# modem.net
KiCad netlist of a schematic drawn in EAGLE
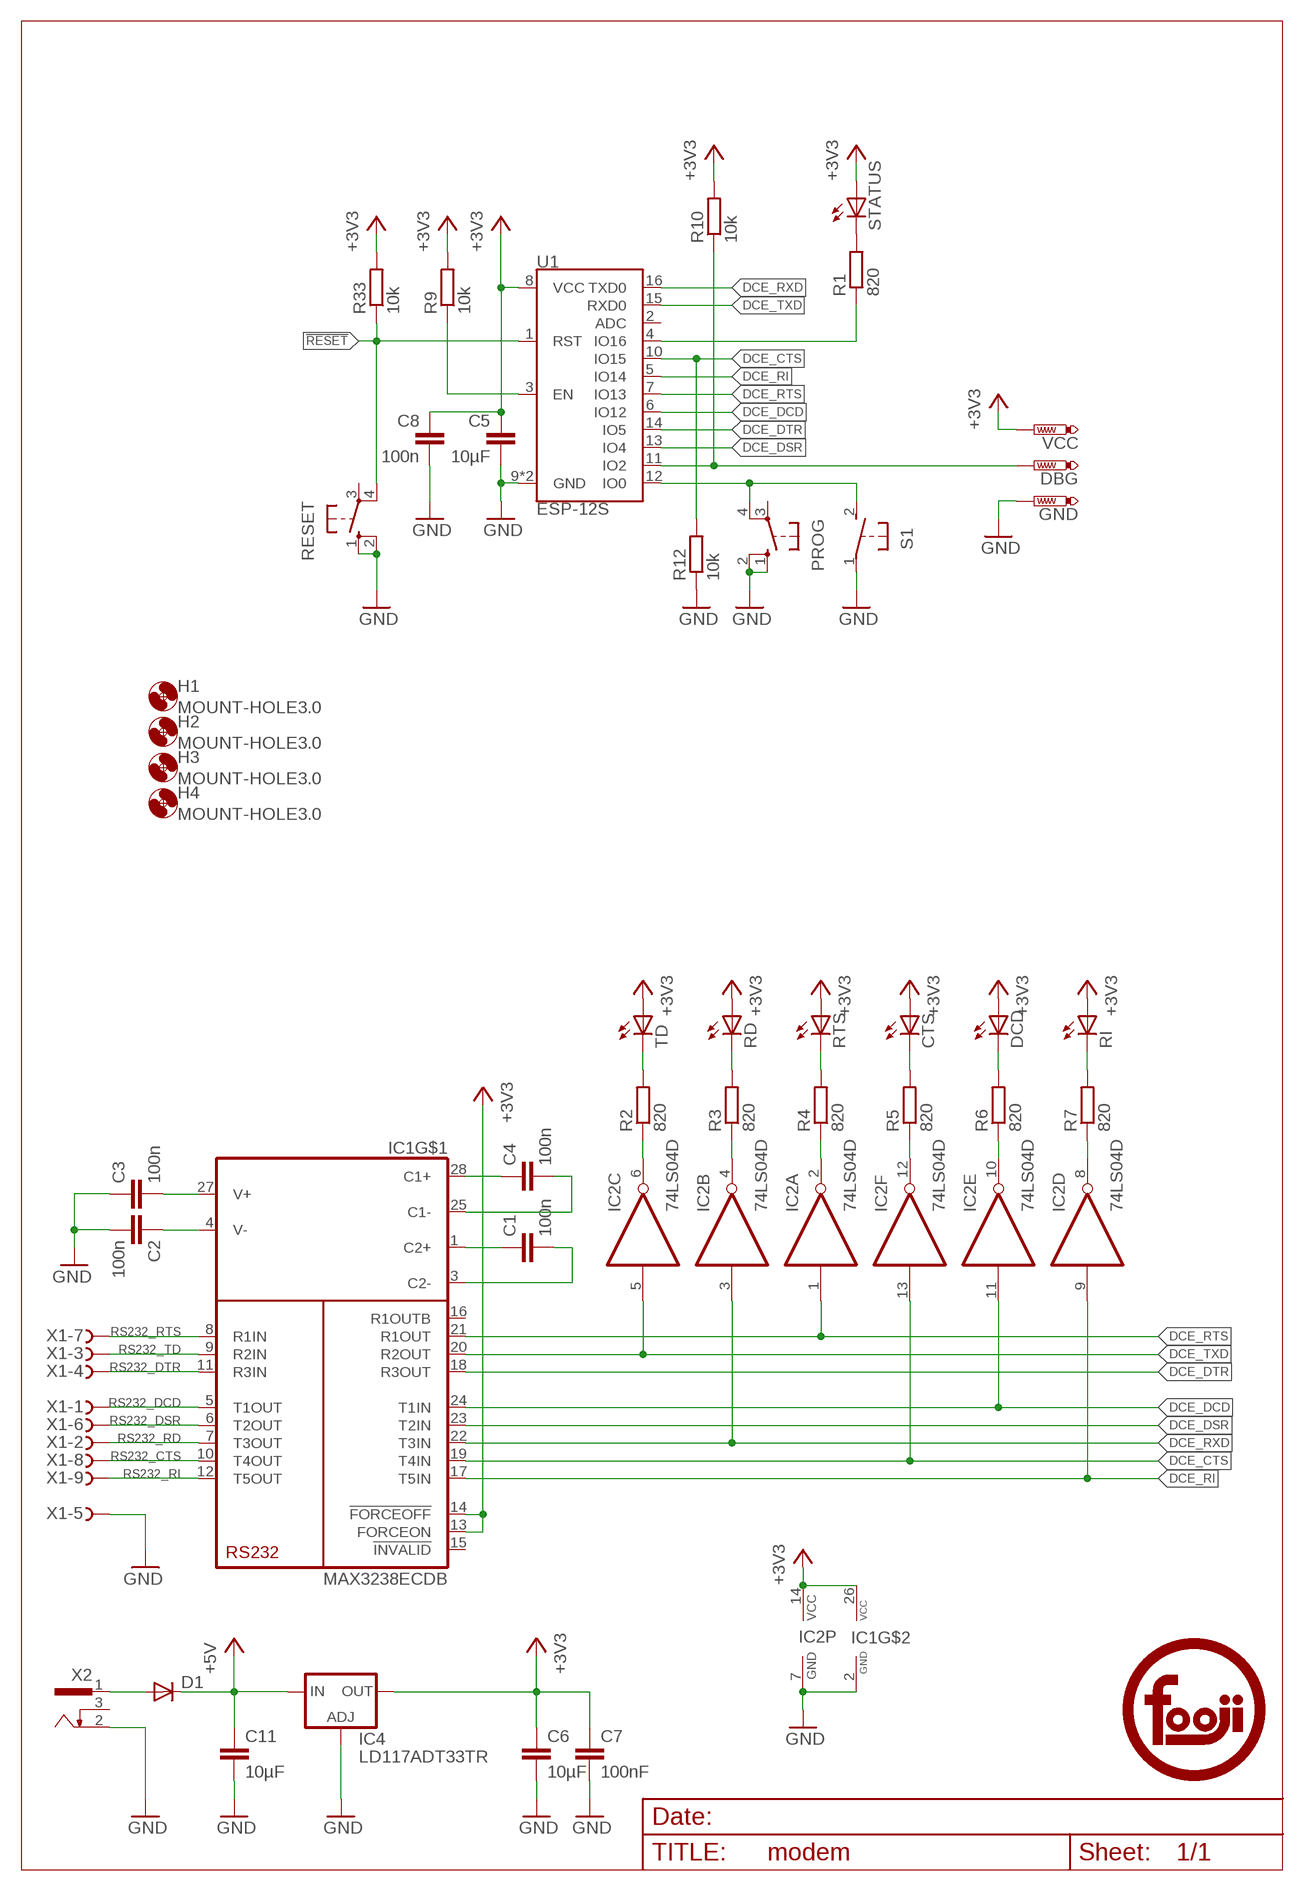
[diagram p0: schematic, sheet 1]

(export (version "E")
  (design (tool "Eeschema 10.0.6"))
  (components
    (comp (ref "C1")
      (value "100n")
      (footprint "eagle-import:C0805")
      (libsource (lib "eagle-import") (part "C-EUC0805"))
    )
    (comp (ref "C2")
      (value "100n")
      (footprint "eagle-import:C0805")
      (libsource (lib "eagle-import") (part "C-EUC0805"))
    )
    (comp (ref "C3")
      (value "100n")
      (footprint "eagle-import:C0805")
      (libsource (lib "eagle-import") (part "C-EUC0805"))
    )
    (comp (ref "C4")
      (value "100n")
      (footprint "eagle-import:C0805")
      (libsource (lib "eagle-import") (part "C-EUC0805"))
    )
    (comp (ref "C5")
      (value "10µF")
      (footprint "eagle-import:C0805")
      (libsource (lib "eagle-import") (part "C-EUC0805"))
    )
    (comp (ref "C6")
      (value "10µF")
      (footprint "eagle-import:C0805")
      (libsource (lib "eagle-import") (part "C-EUC0805"))
    )
    (comp (ref "C7")
      (value "100nF")
      (footprint "eagle-import:C0805")
      (libsource (lib "eagle-import") (part "C-EUC0805"))
    )
    (comp (ref "C8")
      (value "100n")
      (footprint "eagle-import:C0805")
      (libsource (lib "eagle-import") (part "C-EUC0805"))
    )
    (comp (ref "C11")
      (value "10µF")
      (footprint "eagle-import:C0805")
      (libsource (lib "eagle-import") (part "C-EUC0805"))
    )
    (comp (ref "CTS")
      (value "LED5MM")
      (footprint "eagle-import:LED5MM")
      (libsource (lib "eagle-import") (part "LED5MM"))
    )
    (comp (ref "D1")
      (value "DIODE-SMB")
      (footprint "eagle-import:SMB")
      (libsource (lib "eagle-import") (part "DIODE-SMB"))
    )
    (comp (ref "DBG")
      (value "PTR1PAD1-13")
      (footprint "eagle-import:P1-13")
      (libsource (lib "eagle-import") (part "PTR1PAD1-13"))
    )
    (comp (ref "DCD")
      (value "LED5MM")
      (footprint "eagle-import:LED5MM")
      (libsource (lib "eagle-import") (part "LED5MM"))
    )
    (comp (ref "GND")
      (value "PTR1PAD1-13")
      (footprint "eagle-import:P1-13")
      (libsource (lib "eagle-import") (part "PTR1PAD1-13"))
    )
    (comp (ref "H1")
      (value "MOUNT-HOLE3.0")
      (footprint "eagle-import:3,0")
      (libsource (lib "eagle-import") (part "MOUNT-HOLE3.0"))
    )
    (comp (ref "H2")
      (value "MOUNT-HOLE3.0")
      (footprint "eagle-import:3,0")
      (libsource (lib "eagle-import") (part "MOUNT-HOLE3.0"))
    )
    (comp (ref "H3")
      (value "MOUNT-HOLE3.0")
      (footprint "eagle-import:3,0")
      (libsource (lib "eagle-import") (part "MOUNT-HOLE3.0"))
    )
    (comp (ref "H4")
      (value "MOUNT-HOLE3.0")
      (footprint "eagle-import:3,0")
      (libsource (lib "eagle-import") (part "MOUNT-HOLE3.0"))
    )
    (comp (ref "IC1")
      (value "MAX3238ECDB")
      (footprint "eagle-import:SSOP28")
      (libsource (lib "eagle-import") (part "MAX3238ECDB"))
    )
    (comp (ref "IC2")
      (value "74LS04D")
      (footprint "eagle-import:SO14")
      (libsource (lib "eagle-import") (part "7404DLS"))
    )
    (comp (ref "IC4")
      (value "LD117ADT33TR")
      (footprint "eagle-import:DPACK")
      (libsource (lib "eagle-import") (part "LD117A?DT33TR"))
    )
    (comp (ref "PROG")
      (value "10-XX")
      (footprint "eagle-import:B3F-10XX")
      (fields (field (name "MPN") "B3F-1000"))
      (libsource (lib "eagle-import") (part "10-XX"))
    )
    (comp (ref "R1")
      (value "820")
      (footprint "eagle-import:R0805")
      (libsource (lib "eagle-import") (part "R-EU_R0805"))
    )
    (comp (ref "R2")
      (value "820")
      (footprint "eagle-import:R0805")
      (libsource (lib "eagle-import") (part "R-EU_R0805"))
    )
    (comp (ref "R3")
      (value "820")
      (footprint "eagle-import:R0805")
      (libsource (lib "eagle-import") (part "R-EU_R0805"))
    )
    (comp (ref "R4")
      (value "820")
      (footprint "eagle-import:R0805")
      (libsource (lib "eagle-import") (part "R-EU_R0805"))
    )
    (comp (ref "R5")
      (value "820")
      (footprint "eagle-import:R0805")
      (libsource (lib "eagle-import") (part "R-EU_R0805"))
    )
    (comp (ref "R6")
      (value "820")
      (footprint "eagle-import:R0805")
      (libsource (lib "eagle-import") (part "R-EU_R0805"))
    )
    (comp (ref "R7")
      (value "820")
      (footprint "eagle-import:R0805")
      (libsource (lib "eagle-import") (part "R-EU_R0805"))
    )
    (comp (ref "R9")
      (value "10k")
      (footprint "eagle-import:R0805")
      (libsource (lib "eagle-import") (part "R-EU_R0805"))
    )
    (comp (ref "R10")
      (value "10k")
      (footprint "eagle-import:R0805")
      (libsource (lib "eagle-import") (part "R-EU_R0805"))
    )
    (comp (ref "R12")
      (value "10k")
      (footprint "eagle-import:R0805")
      (libsource (lib "eagle-import") (part "R-EU_R0805"))
    )
    (comp (ref "R33")
      (value "10k")
      (footprint "eagle-import:R0805")
      (libsource (lib "eagle-import") (part "R-EU_R0805"))
    )
    (comp (ref "RD")
      (value "LED5MM")
      (footprint "eagle-import:LED5MM")
      (libsource (lib "eagle-import") (part "LED5MM"))
    )
    (comp (ref "RESET")
      (value "10-XX")
      (footprint "eagle-import:B3F-10XX")
      (fields (field (name "MPN") "B3F-1000"))
      (libsource (lib "eagle-import") (part "10-XX"))
    )
    (comp (ref "RI")
      (value "LED5MM")
      (footprint "eagle-import:LED5MM")
      (libsource (lib "eagle-import") (part "LED5MM"))
    )
    (comp (ref "RTS")
      (value "LED5MM")
      (footprint "eagle-import:LED5MM")
      (libsource (lib "eagle-import") (part "LED5MM"))
    )
    (comp (ref "S1")
      (value "31-XX")
      (footprint "eagle-import:B3F-31XX")
      (fields (field (name "MPN") "B3F-3100"))
      (libsource (lib "eagle-import") (part "31-XX"))
    )
    (comp (ref "STATUS")
      (value "LED5MM")
      (footprint "eagle-import:LED5MM")
      (libsource (lib "eagle-import") (part "LED5MM"))
    )
    (comp (ref "TD")
      (value "LED5MM")
      (footprint "eagle-import:LED5MM")
      (libsource (lib "eagle-import") (part "LED5MM"))
    )
    (comp (ref "U$3")
      (value "LOGOTOP_NOCIRCLE_TSTOP")
      (footprint "eagle-import:LOGO_TOP_NOCIRCLE_TSTOP")
      (libsource (lib "eagle-import") (part "LOGOTOP_NOCIRCLE_TSTOP"))
    )
    (comp (ref "U1")
      (value "ESP-12S")
      (footprint "eagle-import:ESP-12S")
      (libsource (lib "eagle-import") (part "ESP-12S"))
    )
    (comp (ref "VCC")
      (value "PTR1PAD1-13")
      (footprint "eagle-import:P1-13")
      (libsource (lib "eagle-import") (part "PTR1PAD1-13"))
    )
    (comp (ref "X1")
      (value "F09HPS")
      (footprint "eagle-import:F09HP")
      (libsource (lib "eagle-import") (part "F09HPS"))
    )
    (comp (ref "X2")
      (value "733980-62")
      (footprint "eagle-import:733980-62")
      (libsource (lib "eagle-import") (part "73398?0-62"))
    )
  )
  (nets
    (net (code "1") (name "+3V3") (class "Default")
      (node (ref "C5") (pin "1") (pinfunction "1_1") (pintype "passive"))
      (node (ref "C6") (pin "1") (pinfunction "1_1") (pintype "passive"))
      (node (ref "C7") (pin "1") (pinfunction "1_1") (pintype "passive"))
      (node (ref "C8") (pin "1") (pinfunction "1_1") (pintype "passive"))
      (node (ref "CTS") (pin "A") (pinfunction "A_A") (pintype "passive"))
      (node (ref "DCD") (pin "A") (pinfunction "A_A") (pintype "passive"))
      (node (ref "IC1") (pin "13") (pinfunction "FORCEON_13") (pintype "input"))
      (node (ref "IC1") (pin "14") (pinfunction "~{FORCEOFF}_14") (pintype "input"))
      (node (ref "IC1") (pin "26") (pinfunction "VCC_26") (pintype "power_in"))
      (node (ref "IC2") (pin "14") (pinfunction "VCC_14") (pintype "power_in"))
      (node (ref "IC4") (pin "4") (pinfunction "OUT_4") (pintype "passive"))
      (node (ref "R10") (pin "2") (pinfunction "2_2") (pintype "passive"))
      (node (ref "R33") (pin "2") (pinfunction "2_2") (pintype "passive"))
      (node (ref "R9") (pin "2") (pinfunction "2_2") (pintype "passive"))
      (node (ref "RD") (pin "A") (pinfunction "A_A") (pintype "passive"))
      (node (ref "RI") (pin "A") (pinfunction "A_A") (pintype "passive"))
      (node (ref "RTS") (pin "A") (pinfunction "A_A") (pintype "passive"))
      (node (ref "STATUS") (pin "A") (pinfunction "A_A") (pintype "passive"))
      (node (ref "TD") (pin "A") (pinfunction "A_A") (pintype "passive"))
      (node (ref "U1") (pin "8") (pinfunction "VCC_8") (pintype "bidirectional"))
      (node (ref "VCC") (pin "TP") (pinfunction "TP_TP") (pintype "input"))
    )
    (net (code "2") (name "+5V") (class "Default")
      (node (ref "C11") (pin "1") (pinfunction "1_1") (pintype "passive"))
      (node (ref "D1") (pin "C") (pinfunction "C_C") (pintype "passive"))
      (node (ref "IC4") (pin "3") (pinfunction "IN_3") (pintype "input"))
    )
    (net (code "3") (name "/RS232_CTS") (class "Default")
      (node (ref "IC1") (pin "10") (pinfunction "T4OUT_10") (pintype "input"))
      (node (ref "X1") (pin "8") (pinfunction "F_8") (pintype "passive"))
    )
    (net (code "4") (name "/RS232_DCD") (class "Default")
      (node (ref "IC1") (pin "5") (pinfunction "T1OUT_5") (pintype "output"))
      (node (ref "X1") (pin "1") (pinfunction "F_1") (pintype "passive"))
    )
    (net (code "5") (name "/RS232_DSR") (class "Default")
      (node (ref "IC1") (pin "6") (pinfunction "T2OUT_6") (pintype "output"))
      (node (ref "X1") (pin "6") (pinfunction "F_6") (pintype "passive"))
    )
    (net (code "6") (name "/RS232_DTR") (class "Default")
      (node (ref "IC1") (pin "11") (pinfunction "R3IN_11") (pintype "input"))
      (node (ref "X1") (pin "4") (pinfunction "F_4") (pintype "passive"))
    )
    (net (code "7") (name "/RS232_RD") (class "Default")
      (node (ref "IC1") (pin "7") (pinfunction "T3OUT_7") (pintype "output"))
      (node (ref "X1") (pin "2") (pinfunction "F_2") (pintype "passive"))
    )
    (net (code "8") (name "/RS232_RI") (class "Default")
      (node (ref "IC1") (pin "12") (pinfunction "T5OUT_12") (pintype "input"))
      (node (ref "X1") (pin "9") (pinfunction "F_9") (pintype "passive"))
    )
    (net (code "9") (name "/RS232_RTS") (class "Default")
      (node (ref "IC1") (pin "8") (pinfunction "R1IN_8") (pintype "input"))
      (node (ref "X1") (pin "7") (pinfunction "F_7") (pintype "passive"))
    )
    (net (code "10") (name "/RS232_TD") (class "Default")
      (node (ref "IC1") (pin "9") (pinfunction "R2IN_9") (pintype "input"))
      (node (ref "X1") (pin "3") (pinfunction "F_3") (pintype "passive"))
    )
    (net (code "11") (name "/~{RESET}") (class "Default")
      (node (ref "R33") (pin "1") (pinfunction "1_1") (pintype "passive"))
      (node (ref "RESET") (pin "4") (pinfunction "P1_4") (pintype "passive"))
      (node (ref "U1") (pin "1") (pinfunction "RST_1") (pintype "bidirectional"))
    )
    (net (code "12") (name "DCE_CTS") (class "Default")
      (node (ref "IC1") (pin "19") (pinfunction "T4IN_19") (pintype "output"))
      (node (ref "IC2") (pin "13") (pinfunction "I_13") (pintype "input"))
      (node (ref "R12") (pin "2") (pinfunction "2_2") (pintype "passive"))
      (node (ref "U1") (pin "10") (pinfunction "IO15_10") (pintype "bidirectional"))
    )
    (net (code "13") (name "DCE_DCD") (class "Default")
      (node (ref "IC1") (pin "24") (pinfunction "T1IN_24") (pintype "input"))
      (node (ref "IC2") (pin "11") (pinfunction "I_11") (pintype "input"))
      (node (ref "U1") (pin "6") (pinfunction "IO12_6") (pintype "bidirectional"))
    )
    (net (code "14") (name "DCE_DSR") (class "Default")
      (node (ref "IC1") (pin "23") (pinfunction "T2IN_23") (pintype "input"))
      (node (ref "U1") (pin "13") (pinfunction "IO4_13") (pintype "bidirectional"))
    )
    (net (code "15") (name "DCE_DTR") (class "Default")
      (node (ref "IC1") (pin "18") (pinfunction "R3OUT_18") (pintype "output"))
      (node (ref "U1") (pin "14") (pinfunction "IO5_14") (pintype "bidirectional"))
    )
    (net (code "16") (name "DCE_RI") (class "Default")
      (node (ref "IC1") (pin "17") (pinfunction "T5IN_17") (pintype "output"))
      (node (ref "IC2") (pin "9") (pinfunction "I_9") (pintype "input"))
      (node (ref "U1") (pin "5") (pinfunction "IO14_5") (pintype "bidirectional"))
    )
    (net (code "17") (name "DCE_RTS") (class "Default")
      (node (ref "IC1") (pin "21") (pinfunction "R1OUT_21") (pintype "output"))
      (node (ref "IC2") (pin "1") (pinfunction "I_1") (pintype "input"))
      (node (ref "U1") (pin "7") (pinfunction "IO13_7") (pintype "bidirectional"))
    )
    (net (code "18") (name "DCE_RXD") (class "Default")
      (node (ref "IC1") (pin "22") (pinfunction "T3IN_22") (pintype "input"))
      (node (ref "IC2") (pin "3") (pinfunction "I_3") (pintype "input"))
      (node (ref "U1") (pin "16") (pinfunction "TXD0_16") (pintype "bidirectional"))
    )
    (net (code "19") (name "DCE_TXD") (class "Default")
      (node (ref "IC1") (pin "20") (pinfunction "R2OUT_20") (pintype "output"))
      (node (ref "IC2") (pin "5") (pinfunction "I_5") (pintype "input"))
      (node (ref "U1") (pin "15") (pinfunction "RXD0_15") (pintype "bidirectional"))
    )
    (net (code "20") (name "GND") (class "Default")
      (node (ref "C11") (pin "2") (pinfunction "2_2") (pintype "passive"))
      (node (ref "C2") (pin "2") (pinfunction "2_2") (pintype "passive"))
      (node (ref "C3") (pin "1") (pinfunction "1_1") (pintype "passive"))
      (node (ref "C5") (pin "2") (pinfunction "2_2") (pintype "passive"))
      (node (ref "C6") (pin "2") (pinfunction "2_2") (pintype "passive"))
      (node (ref "C7") (pin "2") (pinfunction "2_2") (pintype "passive"))
      (node (ref "C8") (pin "2") (pinfunction "2_2") (pintype "passive"))
      (node (ref "GND") (pin "TP") (pinfunction "TP_TP") (pintype "input"))
      (node (ref "IC1") (pin "2") (pinfunction "GND_2") (pintype "power_in"))
      (node (ref "IC2") (pin "7") (pinfunction "GND_7") (pintype "power_in"))
      (node (ref "IC4") (pin "1") (pinfunction "ADJ_1") (pintype "input"))
      (node (ref "PROG") (pin "1") (pinfunction "S_1") (pintype "passive"))
      (node (ref "PROG") (pin "2") (pinfunction "S1_2") (pintype "passive"))
      (node (ref "R12") (pin "1") (pinfunction "1_1") (pintype "passive"))
      (node (ref "RESET") (pin "1") (pinfunction "S_1") (pintype "passive"))
      (node (ref "RESET") (pin "2") (pinfunction "S1_2") (pintype "passive"))
      (node (ref "S1") (pin "1") (pinfunction "P_1") (pintype "passive"))
      (node (ref "U1") (pin "9") (pinfunction "GND_9") (pintype "bidirectional"))
      (node (ref "U1") (pin "P$1") (pinfunction "GND_P$1") (pintype "bidirectional"))
      (node (ref "X1") (pin "5") (pinfunction "F_5") (pintype "passive"))
      (node (ref "X2") (pin "2") (pinfunction "2_2") (pintype "passive"))
    )
    (net (code "21") (name "Net-(CTS-C)") (class "Default")
      (node (ref "CTS") (pin "K") (pinfunction "C_K") (pintype "passive"))
      (node (ref "R5") (pin "2") (pinfunction "2_2") (pintype "passive"))
    )
    (net (code "22") (name "Net-(D1-PadA)") (class "Default")
      (node (ref "D1") (pin "A") (pinfunction "A_A") (pintype "passive"))
      (node (ref "X2") (pin "1") (pinfunction "1_1") (pintype "passive"))
    )
    (net (code "23") (name "Net-(DCD-C)") (class "Default")
      (node (ref "DCD") (pin "K") (pinfunction "C_K") (pintype "passive"))
      (node (ref "R6") (pin "2") (pinfunction "2_2") (pintype "passive"))
    )
    (net (code "24") (name "Net-(IC1A-C1+)") (class "Default")
      (node (ref "C4") (pin "1") (pinfunction "1_1") (pintype "passive"))
      (node (ref "IC1") (pin "28") (pinfunction "C1+_28") (pintype "passive"))
    )
    (net (code "25") (name "Net-(IC1A-C1-)") (class "Default")
      (node (ref "C4") (pin "2") (pinfunction "2_2") (pintype "passive"))
      (node (ref "IC1") (pin "25") (pinfunction "C1-_25") (pintype "passive"))
    )
    (net (code "26") (name "Net-(IC1A-C2+)") (class "Default")
      (node (ref "C1") (pin "1") (pinfunction "1_1") (pintype "passive"))
      (node (ref "IC1") (pin "1") (pinfunction "C2+_1") (pintype "passive"))
    )
    (net (code "27") (name "Net-(IC1A-C2-)") (class "Default")
      (node (ref "C1") (pin "2") (pinfunction "2_2") (pintype "passive"))
      (node (ref "IC1") (pin "3") (pinfunction "C2-_3") (pintype "passive"))
    )
    (net (code "28") (name "Net-(IC1A-V+)") (class "Default")
      (node (ref "C3") (pin "2") (pinfunction "2_2") (pintype "passive"))
      (node (ref "IC1") (pin "27") (pinfunction "V+_27") (pintype "passive"))
    )
    (net (code "29") (name "Net-(IC1A-V-)") (class "Default")
      (node (ref "C2") (pin "1") (pinfunction "1_1") (pintype "passive"))
      (node (ref "IC1") (pin "4") (pinfunction "V-_4") (pintype "passive"))
    )
    (net (code "30") (name "Net-(IC2A-O)") (class "Default")
      (node (ref "IC2") (pin "2") (pinfunction "O_2") (pintype "output"))
      (node (ref "R4") (pin "1") (pinfunction "1_1") (pintype "passive"))
    )
    (net (code "31") (name "Net-(IC2B-O)") (class "Default")
      (node (ref "IC2") (pin "4") (pinfunction "O_4") (pintype "output"))
      (node (ref "R3") (pin "1") (pinfunction "1_1") (pintype "passive"))
    )
    (net (code "32") (name "Net-(IC2C-O)") (class "Default")
      (node (ref "IC2") (pin "6") (pinfunction "O_6") (pintype "output"))
      (node (ref "R2") (pin "1") (pinfunction "1_1") (pintype "passive"))
    )
    (net (code "33") (name "Net-(IC2D-O)") (class "Default")
      (node (ref "IC2") (pin "8") (pinfunction "O_8") (pintype "output"))
      (node (ref "R7") (pin "1") (pinfunction "1_1") (pintype "passive"))
    )
    (net (code "34") (name "Net-(IC2E-O)") (class "Default")
      (node (ref "IC2") (pin "10") (pinfunction "O_10") (pintype "output"))
      (node (ref "R6") (pin "1") (pinfunction "1_1") (pintype "passive"))
    )
    (net (code "35") (name "Net-(IC2F-O)") (class "Default")
      (node (ref "IC2") (pin "12") (pinfunction "O_12") (pintype "output"))
      (node (ref "R5") (pin "1") (pinfunction "1_1") (pintype "passive"))
    )
    (net (code "36") (name "Net-(PROG-P1)") (class "Default")
      (node (ref "PROG") (pin "4") (pinfunction "P1_4") (pintype "passive"))
      (node (ref "S1") (pin "2") (pinfunction "S_2") (pintype "passive"))
      (node (ref "U1") (pin "12") (pinfunction "IO0_12") (pintype "bidirectional"))
    )
    (net (code "37") (name "Net-(RD-C)") (class "Default")
      (node (ref "R3") (pin "2") (pinfunction "2_2") (pintype "passive"))
      (node (ref "RD") (pin "K") (pinfunction "C_K") (pintype "passive"))
    )
    (net (code "38") (name "Net-(RI-C)") (class "Default")
      (node (ref "R7") (pin "2") (pinfunction "2_2") (pintype "passive"))
      (node (ref "RI") (pin "K") (pinfunction "C_K") (pintype "passive"))
    )
    (net (code "39") (name "Net-(RTS-C)") (class "Default")
      (node (ref "R4") (pin "2") (pinfunction "2_2") (pintype "passive"))
      (node (ref "RTS") (pin "K") (pinfunction "C_K") (pintype "passive"))
    )
    (net (code "40") (name "Net-(STATUS-C)") (class "Default")
      (node (ref "R1") (pin "2") (pinfunction "2_2") (pintype "passive"))
      (node (ref "STATUS") (pin "K") (pinfunction "C_K") (pintype "passive"))
    )
    (net (code "41") (name "Net-(TD-C)") (class "Default")
      (node (ref "R2") (pin "2") (pinfunction "2_2") (pintype "passive"))
      (node (ref "TD") (pin "K") (pinfunction "C_K") (pintype "passive"))
    )
    (net (code "42") (name "Net-(U1-EN)") (class "Default")
      (node (ref "R9") (pin "1") (pinfunction "1_1") (pintype "passive"))
      (node (ref "U1") (pin "3") (pinfunction "EN_3") (pintype "bidirectional"))
    )
    (net (code "43") (name "Net-(U1-IO2)") (class "Default")
      (node (ref "DBG") (pin "TP") (pinfunction "TP_TP") (pintype "input"))
      (node (ref "R10") (pin "1") (pinfunction "1_1") (pintype "passive"))
      (node (ref "U1") (pin "11") (pinfunction "IO2_11") (pintype "bidirectional"))
    )
    (net (code "44") (name "Net-(U1-IO16)") (class "Default")
      (node (ref "R1") (pin "1") (pinfunction "1_1") (pintype "passive"))
      (node (ref "U1") (pin "4") (pinfunction "IO16_4") (pintype "bidirectional"))
    )
    (net (code "45") (name "unconnected-(IC1A-R1OUTB-Pad16)") (class "Default")
      (node (ref "IC1") (pin "16") (pinfunction "R1OUTB_16") (pintype "output"))
    )
    (net (code "46") (name "unconnected-(IC1A-~{INVALID}-Pad15)") (class "Default")
      (node (ref "IC1") (pin "15") (pinfunction "~{INVALID}_15") (pintype "input"))
    )
    (net (code "47") (name "unconnected-(PROG-P-Pad3)") (class "Default")
      (node (ref "PROG") (pin "3") (pinfunction "P_3") (pintype "passive"))
    )
    (net (code "48") (name "unconnected-(RESET-P-Pad3)") (class "Default")
      (node (ref "RESET") (pin "3") (pinfunction "P_3") (pintype "passive"))
    )
    (net (code "49") (name "unconnected-(U1-ADC-Pad2)") (class "Default")
      (node (ref "U1") (pin "2") (pinfunction "ADC_2") (pintype "bidirectional"))
    )
    (net (code "50") (name "unconnected-(X2-Pad3)") (class "Default")
      (node (ref "X2") (pin "3") (pinfunction "3_3") (pintype "passive"))
    )
  )
)
